# ADC.net
KiCad netlist of a schematic drawn in EasyEDA Pro
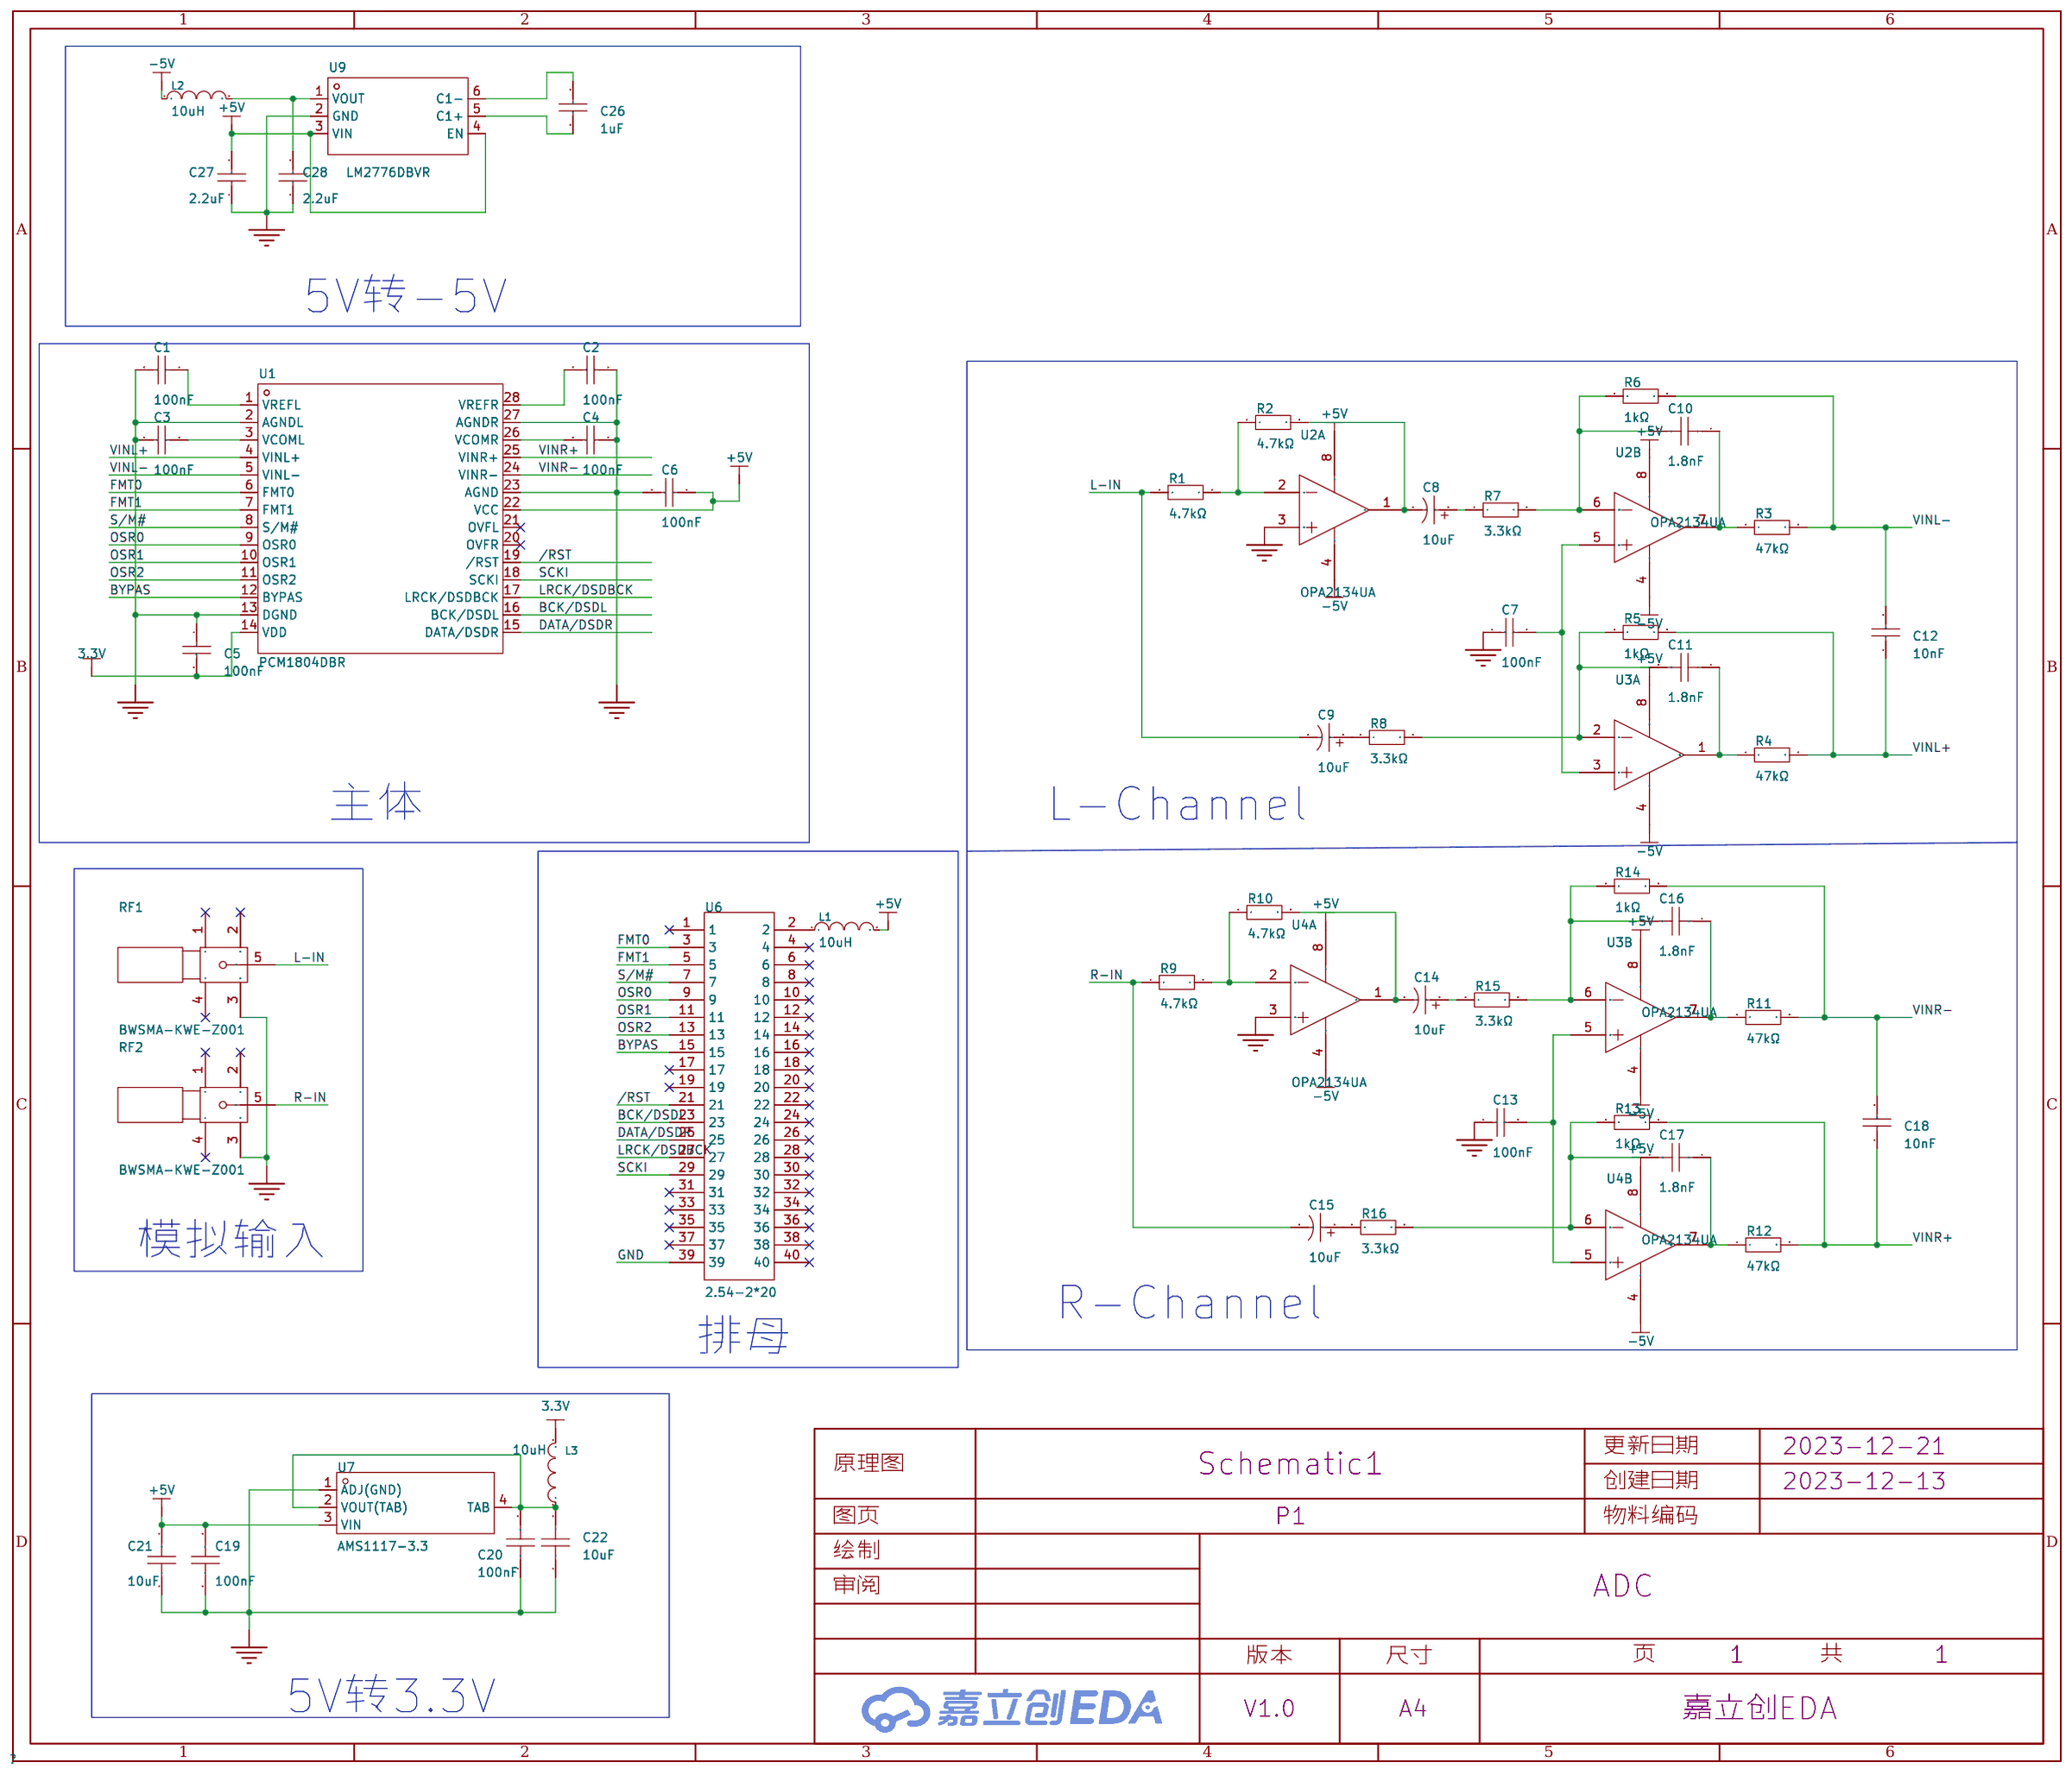
[diagram p0: schematic sheet]

(export (version "E")
  (design (tool "Eeschema 10.0.6"))
  (components
    (comp (ref "C1")
      (value "100nF")
      (footprint "easyedapro:C0805")
      (description "容值:100nF;精度:±10%;额定电压:50V;材质(温度系数):X7R;")
      (fields
        (field (name "Manufacturer Part") "CC0603KRX7R9BB104")
        (field (name "Manufacturer") "YAGEO(国巨)")
      )
      (libsource (lib "easyedapro") (part "CC0805KRX7R9BB104"))
    )
    (comp (ref "C2")
      (value "100nF")
      (footprint "easyedapro:C0805")
      (description "容值:100nF;精度:±10%;额定电压:50V;材质(温度系数):X7R;")
      (fields
        (field (name "Manufacturer Part") "CC0603KRX7R9BB104")
        (field (name "Manufacturer") "YAGEO(国巨)")
      )
      (libsource (lib "easyedapro") (part "CC0805KRX7R9BB104"))
    )
    (comp (ref "C3")
      (value "100nF")
      (footprint "easyedapro:C0805")
      (description "容值:100nF;精度:±10%;额定电压:50V;材质(温度系数):X7R;")
      (fields
        (field (name "Manufacturer Part") "CC0603KRX7R9BB104")
        (field (name "Manufacturer") "YAGEO(国巨)")
      )
      (libsource (lib "easyedapro") (part "CC0805KRX7R9BB104"))
    )
    (comp (ref "C4")
      (value "100nF")
      (footprint "easyedapro:C0805")
      (description "容值:100nF;精度:±10%;额定电压:50V;材质(温度系数):X7R;")
      (fields
        (field (name "Manufacturer Part") "CC0603KRX7R9BB104")
        (field (name "Manufacturer") "YAGEO(国巨)")
      )
      (libsource (lib "easyedapro") (part "CC0805KRX7R9BB104"))
    )
    (comp (ref "C5")
      (value "100nF")
      (footprint "easyedapro:C0805")
      (description "容值:100nF;精度:±10%;额定电压:50V;材质(温度系数):X7R;")
      (fields
        (field (name "Manufacturer Part") "CC0603KRX7R9BB104")
        (field (name "Manufacturer") "YAGEO(国巨)")
      )
      (libsource (lib "easyedapro") (part "CC0805KRX7R9BB104"))
    )
    (comp (ref "C6")
      (value "100nF")
      (footprint "easyedapro:C0805")
      (description "容值:100nF;精度:±10%;额定电压:50V;材质(温度系数):X7R;")
      (fields
        (field (name "Manufacturer Part") "CC0603KRX7R9BB104")
        (field (name "Manufacturer") "YAGEO(国巨)")
      )
      (libsource (lib "easyedapro") (part "CC0805KRX7R9BB104"))
    )
    (comp (ref "C7")
      (value "100nF")
      (footprint "easyedapro:C0805")
      (description "容值:100nF;精度:±10%;额定电压:50V;材质(温度系数):X7R;")
      (fields
        (field (name "Manufacturer Part") "CC0603KRX7R9BB104")
        (field (name "Manufacturer") "YAGEO(国巨)")
      )
      (libsource (lib "easyedapro") (part "CC0805KRX7R9BB104"))
    )
    (comp (ref "C8")
      (value "10uF")
      (footprint "easyedapro:CAP-SMD_BD6.3-L6.6-W6.6-FD")
      (description "容值:10uF;精度:±20%;额定电压:100V;纹波电流:38mA@120Hz;等效串联电阻:-;")
      (fields (field (name "Manufacturer Part") "RVT2A100M0607") (field (name "Manufacturer") "ROQANG(容强)"))
      (libsource (lib "easyedapro") (part "RVT2A100M0607"))
    )
    (comp (ref "C9")
      (value "10uF")
      (footprint "easyedapro:CAP-SMD_BD6.3-L6.6-W6.6-FD")
      (description "容值:10uF;精度:±20%;额定电压:100V;纹波电流:38mA@120Hz;等效串联电阻:-;")
      (fields (field (name "Manufacturer Part") "RVT2A100M0607") (field (name "Manufacturer") "ROQANG(容强)"))
      (libsource (lib "easyedapro") (part "RVT2A100M0607"))
    )
    (comp (ref "C10")
      (value "1.8nF")
      (footprint "easyedapro:C0201")
      (description "容值:1.8nF;精度:±10%;额定电压:25V;材质(温度系数):X7R;")
      (fields (field (name "Manufacturer Part") "0603B182K500NT") (field (name "Manufacturer") "FH(风华)"))
      (libsource (lib "easyedapro") (part "GRM033R71E182KA12D"))
    )
    (comp (ref "C11")
      (value "1.8nF")
      (footprint "easyedapro:C0201")
      (description "容值:1.8nF;精度:±10%;额定电压:25V;材质(温度系数):X7R;")
      (fields (field (name "Manufacturer Part") "0603B182K500NT") (field (name "Manufacturer") "FH(风华)"))
      (libsource (lib "easyedapro") (part "GRM033R71E182KA12D"))
    )
    (comp (ref "C12")
      (value "10nF")
      (footprint "easyedapro:C0402")
      (description "容值:10nF;精度:±10%;额定电压:50V;材质(温度系数):X7R;")
      (fields
        (field (name "Manufacturer Part") "CC0603KRX7R9BB103")
        (field (name "Manufacturer") "YAGEO(国巨)")
      )
      (libsource (lib "easyedapro") (part "CC0402KRX7R9BB103"))
    )
    (comp (ref "C13")
      (value "100nF")
      (footprint "easyedapro:C0805")
      (description "容值:100nF;精度:±10%;额定电压:50V;材质(温度系数):X7R;")
      (fields
        (field (name "Manufacturer Part") "CC0603KRX7R9BB104")
        (field (name "Manufacturer") "YAGEO(国巨)")
      )
      (libsource (lib "easyedapro") (part "CC0805KRX7R9BB104"))
    )
    (comp (ref "C14")
      (value "10uF")
      (footprint "easyedapro:CAP-SMD_BD6.3-L6.6-W6.6-FD")
      (description "容值:10uF;精度:±20%;额定电压:100V;纹波电流:38mA@120Hz;等效串联电阻:-;")
      (fields (field (name "Manufacturer Part") "RVT2A100M0607") (field (name "Manufacturer") "ROQANG(容强)"))
      (libsource (lib "easyedapro") (part "RVT2A100M0607"))
    )
    (comp (ref "C15")
      (value "10uF")
      (footprint "easyedapro:CAP-SMD_BD6.3-L6.6-W6.6-FD")
      (description "容值:10uF;精度:±20%;额定电压:100V;纹波电流:38mA@120Hz;等效串联电阻:-;")
      (fields (field (name "Manufacturer Part") "RVT2A100M0607") (field (name "Manufacturer") "ROQANG(容强)"))
      (libsource (lib "easyedapro") (part "RVT2A100M0607"))
    )
    (comp (ref "C16")
      (value "1.8nF")
      (footprint "easyedapro:C0201")
      (description "容值:1.8nF;精度:±10%;额定电压:25V;材质(温度系数):X7R;")
      (fields (field (name "Manufacturer Part") "0603B182K500NT") (field (name "Manufacturer") "FH(风华)"))
      (libsource (lib "easyedapro") (part "GRM033R71E182KA12D"))
    )
    (comp (ref "C17")
      (value "1.8nF")
      (footprint "easyedapro:C0201")
      (description "容值:1.8nF;精度:±10%;额定电压:25V;材质(温度系数):X7R;")
      (fields (field (name "Manufacturer Part") "0603B182K500NT") (field (name "Manufacturer") "FH(风华)"))
      (libsource (lib "easyedapro") (part "GRM033R71E182KA12D"))
    )
    (comp (ref "C18")
      (value "10nF")
      (footprint "easyedapro:C0402")
      (description "容值:10nF;精度:±10%;额定电压:50V;材质(温度系数):X7R;")
      (fields
        (field (name "Manufacturer Part") "CC0603KRX7R9BB103")
        (field (name "Manufacturer") "YAGEO(国巨)")
      )
      (libsource (lib "easyedapro") (part "CC0402KRX7R9BB103"))
    )
    (comp (ref "C19")
      (value "100nF")
      (footprint "easyedapro:C0603")
      (description "容值:100nF;精度:±10%;额定电压:50V;材质(温度系数):X7R;")
      (fields
        (field (name "Manufacturer Part") "CC0603KRX7R9BB104")
        (field (name "Manufacturer") "YAGEO(国巨)")
      )
      (libsource (lib "easyedapro") (part "CC0603KRX7R9BB104"))
    )
    (comp (ref "C20")
      (value "100nF")
      (footprint "easyedapro:C0603")
      (description "容值:100nF;精度:±10%;额定电压:50V;材质(温度系数):X7R;")
      (fields
        (field (name "Manufacturer Part") "CC0603KRX7R9BB104")
        (field (name "Manufacturer") "YAGEO(国巨)")
      )
      (libsource (lib "easyedapro") (part "CC0603KRX7R9BB104"))
    )
    (comp (ref "C21")
      (value "10uF")
      (footprint "easyedapro:C0603")
      (description "容值:10uF;精度:±10%;额定电压:10V;材质(温度系数):X5R;")
      (fields
        (field (name "Manufacturer Part") "CL10A106KP8NNNC")
        (field (name "Manufacturer") "SAMSUNG(三星)")
      )
      (libsource (lib "easyedapro") (part "CL10A106KP8NNNC"))
    )
    (comp (ref "C22")
      (value "10uF")
      (footprint "easyedapro:C0603")
      (description "容值:10uF;精度:±10%;额定电压:10V;材质(温度系数):X5R;")
      (fields
        (field (name "Manufacturer Part") "CL10A106KP8NNNC")
        (field (name "Manufacturer") "SAMSUNG(三星)")
      )
      (libsource (lib "easyedapro") (part "CL10A106KP8NNNC"))
    )
    (comp (ref "C26")
      (value "1uF")
      (footprint "easyedapro:C0603")
      (description "容值:1uF;精度:±10%;额定电压:50V;材质(温度系数):X5R;")
      (fields
        (field (name "Manufacturer Part") "CL10A105KB8NNNC")
        (field (name "Manufacturer") "SAMSUNG(三星)")
      )
      (libsource (lib "easyedapro") (part "CL10A105KB8NNNC"))
    )
    (comp (ref "C27")
      (value "2.2uF")
      (footprint "easyedapro:C0603")
      (description "容值:2.2uF;精度:±10%;额定电压:16V;材质(温度系数):X5R;")
      (fields
        (field (name "Manufacturer Part") "CL10A225KO8NNNC")
        (field (name "Manufacturer") "SAMSUNG(三星)")
      )
      (libsource (lib "easyedapro") (part "CL10A225KO8NNNC"))
    )
    (comp (ref "C28")
      (value "2.2uF")
      (footprint "easyedapro:C0603")
      (description "容值:2.2uF;精度:±10%;额定电压:16V;材质(温度系数):X5R;")
      (fields
        (field (name "Manufacturer Part") "CL10A225KO8NNNC")
        (field (name "Manufacturer") "SAMSUNG(三星)")
      )
      (libsource (lib "easyedapro") (part "CL10A225KO8NNNC"))
    )
    (comp (ref "L1")
      (value "10uH")
      (footprint "easyedapro:L0603")
      (description "电感值:10uH;精度:±10%;额定电流:3mA;饱和电流(Isat):-;直流电阻(DCR):1.85Ω;")
      (fields
        (field (name "Manufacturer Part") "SDFL1608S100KTF")
        (field (name "Manufacturer") "Sunlord(顺络)")
      )
      (libsource (lib "easyedapro") (part "SDFL1608S100KTF"))
    )
    (comp (ref "L2")
      (value "10uH")
      (footprint "easyedapro:L0603")
      (description "电感值:10uH;精度:±10%;额定电流:3mA;饱和电流(Isat):-;直流电阻(DCR):1.85Ω;")
      (fields
        (field (name "Manufacturer Part") "SDFL1608S100KTF")
        (field (name "Manufacturer") "Sunlord(顺络)")
      )
      (libsource (lib "easyedapro") (part "SDFL1608S100KTF"))
    )
    (comp (ref "L3")
      (value "10uH")
      (footprint "easyedapro:L0603")
      (description "电感值:10uH;精度:±10%;额定电流:3mA;饱和电流(Isat):-;直流电阻(DCR):1.85Ω;")
      (fields
        (field (name "Manufacturer Part") "SDFL1608S100KTF")
        (field (name "Manufacturer") "Sunlord(顺络)")
      )
      (libsource (lib "easyedapro") (part "SDFL1608S100KTF"))
    )
    (comp (ref "R1")
      (value "4.7kΩ")
      (footprint "easyedapro:R0603")
      (description "阻值:4.7kΩ;精度:±1%;功率:100mW;温度系数:±100ppm/°C;电阻类型:厚膜电阻;")
      (fields
        (field (name "Manufacturer Part") "0603WAF4701T5E")
        (field (name "Manufacturer") "UNI-ROYAL(厚声)")
      )
      (libsource (lib "easyedapro") (part "0603WAF4701T5E"))
    )
    (comp (ref "R2")
      (value "4.7kΩ")
      (footprint "easyedapro:R0603")
      (description "阻值:4.7kΩ;精度:±1%;功率:100mW;温度系数:±100ppm/°C;电阻类型:厚膜电阻;")
      (fields
        (field (name "Manufacturer Part") "0603WAF4701T5E")
        (field (name "Manufacturer") "UNI-ROYAL(厚声)")
      )
      (libsource (lib "easyedapro") (part "0603WAF4701T5E"))
    )
    (comp (ref "R3")
      (value "47kΩ")
      (footprint "easyedapro:R0603")
      (description "阻值:47kΩ;精度:±1%;功率:100mW;温度系数:±100ppm/°C;电阻类型:厚膜电阻;")
      (fields
        (field (name "Manufacturer Part") "0603WAF4702T5E")
        (field (name "Manufacturer") "UNI-ROYAL(厚声)")
      )
      (libsource (lib "easyedapro") (part "0603WAF4702T5E"))
    )
    (comp (ref "R4")
      (value "47kΩ")
      (footprint "easyedapro:R0603")
      (description "阻值:47kΩ;精度:±1%;功率:100mW;温度系数:±100ppm/°C;电阻类型:厚膜电阻;")
      (fields
        (field (name "Manufacturer Part") "0603WAF4702T5E")
        (field (name "Manufacturer") "UNI-ROYAL(厚声)")
      )
      (libsource (lib "easyedapro") (part "0603WAF4702T5E"))
    )
    (comp (ref "R5")
      (value "1kΩ")
      (footprint "easyedapro:R0805")
      (description "阻值:1kΩ;精度:±1%;功率:125mW;温度系数:±100ppm/°C;电阻类型:厚膜电阻;")
      (fields
        (field (name "Manufacturer Part") "0603WAF1001T5E")
        (field (name "Manufacturer") "UNI-ROYAL(厚声)")
      )
      (libsource (lib "easyedapro") (part "0805W8F1001T5E"))
    )
    (comp (ref "R6")
      (value "1kΩ")
      (footprint "easyedapro:R0805")
      (description "阻值:1kΩ;精度:±1%;功率:125mW;温度系数:±100ppm/°C;电阻类型:厚膜电阻;")
      (fields
        (field (name "Manufacturer Part") "0603WAF1001T5E")
        (field (name "Manufacturer") "UNI-ROYAL(厚声)")
      )
      (libsource (lib "easyedapro") (part "0805W8F1001T5E"))
    )
    (comp (ref "R7")
      (value "3.3kΩ")
      (footprint "easyedapro:R0603")
      (description "阻值:3.3kΩ;精度:±1%;功率:100mW;温度系数:±100ppm/°C;电阻类型:厚膜电阻;")
      (fields
        (field (name "Manufacturer Part") "0603WAF3301T5E")
        (field (name "Manufacturer") "UNI-ROYAL(厚声)")
      )
      (libsource (lib "easyedapro") (part "0603WAF3301T5E"))
    )
    (comp (ref "R8")
      (value "3.3kΩ")
      (footprint "easyedapro:R0603")
      (description "阻值:3.3kΩ;精度:±1%;功率:100mW;温度系数:±100ppm/°C;电阻类型:厚膜电阻;")
      (fields
        (field (name "Manufacturer Part") "0603WAF3301T5E")
        (field (name "Manufacturer") "UNI-ROYAL(厚声)")
      )
      (libsource (lib "easyedapro") (part "0603WAF3301T5E"))
    )
    (comp (ref "R9")
      (value "4.7kΩ")
      (footprint "easyedapro:R0603")
      (description "阻值:4.7kΩ;精度:±1%;功率:100mW;温度系数:±100ppm/°C;电阻类型:厚膜电阻;")
      (fields
        (field (name "Manufacturer Part") "0603WAF4701T5E")
        (field (name "Manufacturer") "UNI-ROYAL(厚声)")
      )
      (libsource (lib "easyedapro") (part "0603WAF4701T5E"))
    )
    (comp (ref "R10")
      (value "4.7kΩ")
      (footprint "easyedapro:R0603")
      (description "阻值:4.7kΩ;精度:±1%;功率:100mW;温度系数:±100ppm/°C;电阻类型:厚膜电阻;")
      (fields
        (field (name "Manufacturer Part") "0603WAF4701T5E")
        (field (name "Manufacturer") "UNI-ROYAL(厚声)")
      )
      (libsource (lib "easyedapro") (part "0603WAF4701T5E"))
    )
    (comp (ref "R11")
      (value "47kΩ")
      (footprint "easyedapro:R0603")
      (description "阻值:47kΩ;精度:±1%;功率:100mW;温度系数:±100ppm/°C;电阻类型:厚膜电阻;")
      (fields
        (field (name "Manufacturer Part") "0603WAF4702T5E")
        (field (name "Manufacturer") "UNI-ROYAL(厚声)")
      )
      (libsource (lib "easyedapro") (part "0603WAF4702T5E"))
    )
    (comp (ref "R12")
      (value "47kΩ")
      (footprint "easyedapro:R0603")
      (description "阻值:47kΩ;精度:±1%;功率:100mW;温度系数:±100ppm/°C;电阻类型:厚膜电阻;")
      (fields
        (field (name "Manufacturer Part") "0603WAF4702T5E")
        (field (name "Manufacturer") "UNI-ROYAL(厚声)")
      )
      (libsource (lib "easyedapro") (part "0603WAF4702T5E"))
    )
    (comp (ref "R13")
      (value "1kΩ")
      (footprint "easyedapro:R0805")
      (description "阻值:1kΩ;精度:±1%;功率:125mW;温度系数:±100ppm/°C;电阻类型:厚膜电阻;")
      (fields
        (field (name "Manufacturer Part") "0603WAF1001T5E")
        (field (name "Manufacturer") "UNI-ROYAL(厚声)")
      )
      (libsource (lib "easyedapro") (part "0805W8F1001T5E"))
    )
    (comp (ref "R14")
      (value "1kΩ")
      (footprint "easyedapro:R0805")
      (description "阻值:1kΩ;精度:±1%;功率:125mW;温度系数:±100ppm/°C;电阻类型:厚膜电阻;")
      (fields
        (field (name "Manufacturer Part") "0603WAF1001T5E")
        (field (name "Manufacturer") "UNI-ROYAL(厚声)")
      )
      (libsource (lib "easyedapro") (part "0805W8F1001T5E"))
    )
    (comp (ref "R15")
      (value "3.3kΩ")
      (footprint "easyedapro:R0603")
      (description "阻值:3.3kΩ;精度:±1%;功率:100mW;温度系数:±100ppm/°C;电阻类型:厚膜电阻;")
      (fields
        (field (name "Manufacturer Part") "0603WAF3301T5E")
        (field (name "Manufacturer") "UNI-ROYAL(厚声)")
      )
      (libsource (lib "easyedapro") (part "0603WAF3301T5E"))
    )
    (comp (ref "R16")
      (value "3.3kΩ")
      (footprint "easyedapro:R0603")
      (description "阻值:3.3kΩ;精度:±1%;功率:100mW;温度系数:±100ppm/°C;电阻类型:厚膜电阻;")
      (fields
        (field (name "Manufacturer Part") "0603WAF3301T5E")
        (field (name "Manufacturer") "UNI-ROYAL(厚声)")
      )
      (libsource (lib "easyedapro") (part "0603WAF3301T5E"))
    )
    (comp (ref "RF1")
      (value "BWSMA-KWE-Z001")
      (footprint "easyedapro:SMA-TH_BWSMA-KWE-Z001")
      (fields (field (name "Manufacturer") "BAT WIRELESS(蝙蝠无线)"))
      (libsource (lib "easyedapro") (part "BWSMA-KWE-Z001"))
    )
    (comp (ref "RF2")
      (value "BWSMA-KWE-Z001")
      (footprint "easyedapro:SMA-TH_BWSMA-KWE-Z001")
      (fields (field (name "Manufacturer") "BAT WIRELESS(蝙蝠无线)"))
      (libsource (lib "easyedapro") (part "BWSMA-KWE-Z001"))
    )
    (comp (ref "U1")
      (value "PCM1804DBR")
      (footprint "easyedapro:SSOP-28_L10.2-W5.3-P0.65-LS7.8-BL")
      (description "供电电压:3V~3.6V；4.75V~5.25V;分辨率(位):24;接口类型:I2S;")
      (fields (field (name "Manufacturer") "TI(德州仪器)"))
      (libsource (lib "easyedapro") (part "PCM1804DBR"))
    )
    (comp (ref "U2")
      (value "OPA2134UA")
      (footprint "easyedapro:DIP-8_L9.6-W6.4-P2.54-LS7.6-BL-1")
      (description "功放类型:-;输出功率:-;")
      (fields (field (name "Manufacturer") "TI(德州仪器)"))
      (libsource (lib "easyedapro") (part "OPA2134PA"))
    )
    (comp (ref "U3")
      (value "OPA2134UA")
      (footprint "easyedapro:DIP-8_L9.6-W6.4-P2.54-LS7.6-BL-1")
      (description "功放类型:-;输出功率:-;")
      (fields (field (name "Manufacturer") "TI(德州仪器)"))
      (libsource (lib "easyedapro") (part "OPA2134PA"))
    )
    (comp (ref "U4")
      (value "OPA2134UA")
      (footprint "easyedapro:DIP-8_L9.6-W6.4-P2.54-LS7.6-BL-1")
      (description "功放类型:-;输出功率:-;")
      (fields (field (name "Manufacturer") "TI(德州仪器)"))
      (libsource (lib "easyedapro") (part "OPA2134PA"))
    )
    (comp (ref "U6")
      (value "2.54-2*20")
      (footprint "easyedapro:HDR-TH_40P-P2.54-V-F-R2-C20-S2.54")
      (fields (field (name "Manufacturer") "ZHOURI(洲日)"))
      (libsource (lib "easyedapro") (part "2.54-2*20"))
    )
    (comp (ref "U7")
      (value "AMS1117-3.3")
      (footprint "easyedapro:SOT-223-4_L6.5-W3.5-P2.30-LS7.0-BR")
      (description "输出类型:固定;最大输入电压:18V;输出电压:3.3V;输出电流:1A;电源纹波抑制比(PSRR):60dB@(120Hz);输出极性:正;")
      (fields (field (name "Manufacturer") "UMW(友台半导体)"))
      (libsource (lib "easyedapro") (part "AMS1117-3.3_C347222"))
    )
    (comp (ref "U9")
      (value "LM2776DBVR")
      (footprint "easyedapro:SOT-23-6_L2.9-W1.6-P0.95-LS2.8-BR")
      (description "功能类型:电荷泵;输出类型:固定;输入电压:2.7V~5.5V;输出电压:-5.5V~-2.7V;输出电流(最大值):200mA;")
      (fields (field (name "Manufacturer") "TI(德州仪器)"))
      (libsource (lib "easyedapro") (part "LM2776DBVR"))
    )
  )
  (nets
    (net (code "1") (name "+5V") (class "Default")
      (node (ref "C19") (pin "2") (pinfunction "2_2") (pintype "unspecified"))
      (node (ref "C21") (pin "2") (pinfunction "2_2") (pintype "unspecified"))
      (node (ref "C27") (pin "2") (pinfunction "2_2") (pintype "input"))
      (node (ref "C6") (pin "1") (pinfunction "1_1") (pintype "input"))
      (node (ref "L1") (pin "2") (pinfunction "2_2") (pintype "input"))
      (node (ref "U1") (pin "22") (pinfunction "VCC_22") (pintype "unspecified"))
      (node (ref "U2") (pin "8") (pinfunction "V+_8") (pintype "input"))
      (node (ref "U3") (pin "8") (pinfunction "V+_8") (pintype "input"))
      (node (ref "U4") (pin "8") (pinfunction "V+_8") (pintype "input"))
      (node (ref "U7") (pin "3") (pinfunction "VIN_3") (pintype "unspecified"))
      (node (ref "U9") (pin "3") (pinfunction "VIN_3") (pintype "unspecified"))
      (node (ref "U9") (pin "4") (pinfunction "EN_4") (pintype "unspecified"))
    )
    (net (code "2") (name "-5V") (class "Default")
      (node (ref "L2") (pin "1") (pinfunction "1_1") (pintype "input"))
      (node (ref "U2") (pin "4") (pinfunction "V-_4") (pintype "input"))
      (node (ref "U3") (pin "4") (pinfunction "V-_4") (pintype "input"))
      (node (ref "U4") (pin "4") (pinfunction "V-_4") (pintype "input"))
    )
    (net (code "3") (name "/BCK{slash}DSDL") (class "Default")
      (node (ref "U1") (pin "16") (pinfunction "BCK/DSDL_16") (pintype "unspecified"))
      (node (ref "U6") (pin "23") (pinfunction "23_23") (pintype "unspecified"))
    )
    (net (code "4") (name "/BYPAS") (class "Default")
      (node (ref "U1") (pin "12") (pinfunction "BYPAS_12") (pintype "unspecified"))
      (node (ref "U6") (pin "15") (pinfunction "15_15") (pintype "unspecified"))
    )
    (net (code "5") (name "/DATA{slash}DSDR") (class "Default")
      (node (ref "U1") (pin "15") (pinfunction "DATA/DSDR_15") (pintype "unspecified"))
      (node (ref "U6") (pin "25") (pinfunction "25_25") (pintype "unspecified"))
    )
    (net (code "6") (name "/FMT0") (class "Default")
      (node (ref "U1") (pin "6") (pinfunction "FMT0_6") (pintype "unspecified"))
      (node (ref "U6") (pin "3") (pinfunction "3_3") (pintype "unspecified"))
    )
    (net (code "7") (name "/FMT1") (class "Default")
      (node (ref "U1") (pin "7") (pinfunction "FMT1_7") (pintype "unspecified"))
      (node (ref "U6") (pin "5") (pinfunction "5_5") (pintype "unspecified"))
    )
    (net (code "8") (name "/L-IN") (class "Default")
      (node (ref "C9") (pin "2") (pinfunction "2_2") (pintype "input"))
      (node (ref "R1") (pin "1") (pinfunction "1_1") (pintype "input"))
      (node (ref "RF1") (pin "5") (pinfunction "5_5") (pintype "unspecified"))
    )
    (net (code "9") (name "/LRCK{slash}DSDBCK") (class "Default")
      (node (ref "U1") (pin "17") (pinfunction "LRCK/DSDBCK_17") (pintype "unspecified"))
      (node (ref "U6") (pin "27") (pinfunction "27_27") (pintype "unspecified"))
    )
    (net (code "10") (name "/OSR0") (class "Default")
      (node (ref "U1") (pin "9") (pinfunction "OSR0_9") (pintype "unspecified"))
      (node (ref "U6") (pin "9") (pinfunction "9_9") (pintype "unspecified"))
    )
    (net (code "11") (name "/OSR1") (class "Default")
      (node (ref "U1") (pin "10") (pinfunction "OSR1_10") (pintype "unspecified"))
      (node (ref "U6") (pin "11") (pinfunction "11_11") (pintype "unspecified"))
    )
    (net (code "12") (name "/OSR2") (class "Default")
      (node (ref "U1") (pin "11") (pinfunction "OSR2_11") (pintype "unspecified"))
      (node (ref "U6") (pin "13") (pinfunction "13_13") (pintype "unspecified"))
    )
    (net (code "13") (name "/R-IN") (class "Default")
      (node (ref "C15") (pin "2") (pinfunction "2_2") (pintype "input"))
      (node (ref "R9") (pin "1") (pinfunction "1_1") (pintype "input"))
      (node (ref "RF2") (pin "5") (pinfunction "5_5") (pintype "unspecified"))
    )
    (net (code "14") (name "/SCKI") (class "Default")
      (node (ref "U1") (pin "18") (pinfunction "SCKI_18") (pintype "unspecified"))
      (node (ref "U6") (pin "29") (pinfunction "29_29") (pintype "unspecified"))
    )
    (net (code "15") (name "/S{slash}M#") (class "Default")
      (node (ref "U1") (pin "8") (pinfunction "S/M#_8") (pintype "unspecified"))
      (node (ref "U6") (pin "7") (pinfunction "7_7") (pintype "unspecified"))
    )
    (net (code "16") (name "/VINL+") (class "Default")
      (node (ref "C12") (pin "1") (pinfunction "1_1") (pintype "input"))
      (node (ref "R4") (pin "2") (pinfunction "2_2") (pintype "input"))
      (node (ref "R5") (pin "2") (pinfunction "2_2") (pintype "input"))
      (node (ref "U1") (pin "4") (pinfunction "VINL+_4") (pintype "unspecified"))
    )
    (net (code "17") (name "/VINL-") (class "Default")
      (node (ref "C12") (pin "2") (pinfunction "2_2") (pintype "input"))
      (node (ref "R3") (pin "2") (pinfunction "2_2") (pintype "input"))
      (node (ref "R6") (pin "2") (pinfunction "2_2") (pintype "input"))
      (node (ref "U1") (pin "5") (pinfunction "VINL-_5") (pintype "unspecified"))
    )
    (net (code "18") (name "/VINR+") (class "Default")
      (node (ref "C18") (pin "1") (pinfunction "1_1") (pintype "input"))
      (node (ref "R12") (pin "2") (pinfunction "2_2") (pintype "input"))
      (node (ref "R13") (pin "2") (pinfunction "2_2") (pintype "input"))
      (node (ref "U1") (pin "25") (pinfunction "VINR+_25") (pintype "unspecified"))
    )
    (net (code "19") (name "/VINR-") (class "Default")
      (node (ref "C18") (pin "2") (pinfunction "2_2") (pintype "input"))
      (node (ref "R11") (pin "2") (pinfunction "2_2") (pintype "input"))
      (node (ref "R14") (pin "2") (pinfunction "2_2") (pintype "input"))
      (node (ref "U1") (pin "24") (pinfunction "VINR-_24") (pintype "unspecified"))
    )
    (net (code "20") (name "/{slash}RST") (class "Default")
      (node (ref "U1") (pin "19") (pinfunction "/RST_19") (pintype "unspecified"))
      (node (ref "U6") (pin "21") (pinfunction "21_21") (pintype "unspecified"))
    )
    (net (code "21") (name "3.3V") (class "Default")
      (node (ref "C5") (pin "2") (pinfunction "2_2") (pintype "input"))
      (node (ref "L3") (pin "2") (pinfunction "2_2") (pintype "input"))
      (node (ref "U1") (pin "14") (pinfunction "VDD_14") (pintype "unspecified"))
    )
    (net (code "22") (name "GND") (class "Default")
      (node (ref "C1") (pin "2") (pinfunction "2_2") (pintype "input"))
      (node (ref "C13") (pin "1") (pinfunction "1_1") (pintype "input"))
      (node (ref "C19") (pin "1") (pinfunction "1_1") (pintype "unspecified"))
      (node (ref "C2") (pin "1") (pinfunction "1_1") (pintype "input"))
      (node (ref "C20") (pin "1") (pinfunction "1_1") (pintype "unspecified"))
      (node (ref "C21") (pin "1") (pinfunction "1_1") (pintype "unspecified"))
      (node (ref "C22") (pin "1") (pinfunction "1_1") (pintype "unspecified"))
      (node (ref "C27") (pin "1") (pinfunction "1_1") (pintype "input"))
      (node (ref "C28") (pin "1") (pinfunction "1_1") (pintype "input"))
      (node (ref "C3") (pin "2") (pinfunction "2_2") (pintype "input"))
      (node (ref "C4") (pin "1") (pinfunction "1_1") (pintype "input"))
      (node (ref "C5") (pin "1") (pinfunction "1_1") (pintype "input"))
      (node (ref "C6") (pin "2") (pinfunction "2_2") (pintype "input"))
      (node (ref "C7") (pin "1") (pinfunction "1_1") (pintype "input"))
      (node (ref "RF1") (pin "3") (pinfunction "3_3") (pintype "unspecified"))
      (node (ref "RF2") (pin "3") (pinfunction "3_3") (pintype "unspecified"))
      (node (ref "U1") (pin "13") (pinfunction "DGND_13") (pintype "unspecified"))
      (node (ref "U1") (pin "2") (pinfunction "AGNDL_2") (pintype "unspecified"))
      (node (ref "U1") (pin "23") (pinfunction "AGND_23") (pintype "unspecified"))
      (node (ref "U1") (pin "27") (pinfunction "AGNDR_27") (pintype "unspecified"))
      (node (ref "U2") (pin "3") (pinfunction "+IN_A_3") (pintype "input"))
      (node (ref "U4") (pin "3") (pinfunction "+IN_A_3") (pintype "input"))
      (node (ref "U6") (pin "39") (pinfunction "39_39") (pintype "unspecified"))
      (node (ref "U7") (pin "1") (pinfunction "ADJ(GND)_1") (pintype "unspecified"))
      (node (ref "U9") (pin "2") (pinfunction "GND_2") (pintype "unspecified"))
    )
    (net (code "23") (name "Net-(C8-Pad1)") (class "Default")
      (node (ref "C8") (pin "1") (pinfunction "1_1") (pintype "input"))
      (node (ref "R7") (pin "1") (pinfunction "1_1") (pintype "input"))
    )
    (net (code "24") (name "Net-(C9-Pad1)") (class "Default")
      (node (ref "C9") (pin "1") (pinfunction "1_1") (pintype "input"))
      (node (ref "R8") (pin "1") (pinfunction "1_1") (pintype "input"))
    )
    (net (code "25") (name "Net-(C14-Pad1)") (class "Default")
      (node (ref "C14") (pin "1") (pinfunction "1_1") (pintype "input"))
      (node (ref "R15") (pin "1") (pinfunction "1_1") (pintype "input"))
    )
    (net (code "26") (name "Net-(C15-Pad1)") (class "Default")
      (node (ref "C15") (pin "1") (pinfunction "1_1") (pintype "input"))
      (node (ref "R16") (pin "1") (pinfunction "1_1") (pintype "input"))
    )
    (net (code "27") (name "Net-(L1-Pad1)") (class "Default")
      (node (ref "L1") (pin "1") (pinfunction "1_1") (pintype "input"))
      (node (ref "U6") (pin "2") (pinfunction "2_2") (pintype "unspecified"))
    )
    (net (code "28") (name "Net-(U1-VCOML)") (class "Default")
      (node (ref "C3") (pin "1") (pinfunction "1_1") (pintype "input"))
      (node (ref "U1") (pin "3") (pinfunction "VCOML_3") (pintype "unspecified"))
    )
    (net (code "29") (name "Net-(U1-VCOMR)") (class "Default")
      (node (ref "C4") (pin "2") (pinfunction "2_2") (pintype "input"))
      (node (ref "U1") (pin "26") (pinfunction "VCOMR_26") (pintype "unspecified"))
    )
    (net (code "30") (name "Net-(U1-VREFL)") (class "Default")
      (node (ref "C1") (pin "1") (pinfunction "1_1") (pintype "input"))
      (node (ref "U1") (pin "1") (pinfunction "VREFL_1") (pintype "unspecified"))
    )
    (net (code "31") (name "Net-(U1-VREFR)") (class "Default")
      (node (ref "C2") (pin "2") (pinfunction "2_2") (pintype "input"))
      (node (ref "U1") (pin "28") (pinfunction "VREFR_28") (pintype "unspecified"))
    )
    (net (code "32") (name "Net-(U2A--IN_A)") (class "Default")
      (node (ref "R1") (pin "2") (pinfunction "2_2") (pintype "input"))
      (node (ref "R2") (pin "1") (pinfunction "1_1") (pintype "input"))
      (node (ref "U2") (pin "2") (pinfunction "-IN_A_2") (pintype "input"))
    )
    (net (code "33") (name "Net-(U2A-OUT_A)") (class "Default")
      (node (ref "C8") (pin "2") (pinfunction "2_2") (pintype "input"))
      (node (ref "R2") (pin "2") (pinfunction "2_2") (pintype "input"))
      (node (ref "U2") (pin "1") (pinfunction "OUT_A_1") (pintype "output"))
    )
    (net (code "34") (name "Net-(U2B-+IN_B)") (class "Default")
      (node (ref "C7") (pin "2") (pinfunction "2_2") (pintype "input"))
      (node (ref "U2") (pin "5") (pinfunction "+IN_B_5") (pintype "input"))
      (node (ref "U3") (pin "3") (pinfunction "+IN_A_3") (pintype "input"))
    )
    (net (code "35") (name "Net-(U2B--IN_B)") (class "Default")
      (node (ref "C10") (pin "2") (pinfunction "2_2") (pintype "unspecified"))
      (node (ref "R6") (pin "1") (pinfunction "1_1") (pintype "input"))
      (node (ref "R7") (pin "2") (pinfunction "2_2") (pintype "input"))
      (node (ref "U2") (pin "6") (pinfunction "-IN_B_6") (pintype "input"))
    )
    (net (code "36") (name "Net-(U2B-OUT_B)") (class "Default")
      (node (ref "C10") (pin "1") (pinfunction "1_1") (pintype "unspecified"))
      (node (ref "R3") (pin "1") (pinfunction "1_1") (pintype "input"))
      (node (ref "U2") (pin "7") (pinfunction "OUT_B_7") (pintype "output"))
    )
    (net (code "37") (name "Net-(U3A--IN_A)") (class "Default")
      (node (ref "C11") (pin "2") (pinfunction "2_2") (pintype "unspecified"))
      (node (ref "R5") (pin "1") (pinfunction "1_1") (pintype "input"))
      (node (ref "R8") (pin "2") (pinfunction "2_2") (pintype "input"))
      (node (ref "U3") (pin "2") (pinfunction "-IN_A_2") (pintype "input"))
    )
    (net (code "38") (name "Net-(U3A-OUT_A)") (class "Default")
      (node (ref "C11") (pin "1") (pinfunction "1_1") (pintype "unspecified"))
      (node (ref "R4") (pin "1") (pinfunction "1_1") (pintype "input"))
      (node (ref "U3") (pin "1") (pinfunction "OUT_A_1") (pintype "output"))
    )
    (net (code "39") (name "Net-(U3B-+IN_B)") (class "Default")
      (node (ref "C13") (pin "2") (pinfunction "2_2") (pintype "input"))
      (node (ref "U3") (pin "5") (pinfunction "+IN_B_5") (pintype "input"))
      (node (ref "U4") (pin "5") (pinfunction "+IN_B_5") (pintype "input"))
    )
    (net (code "40") (name "Net-(U3B--IN_B)") (class "Default")
      (node (ref "C16") (pin "2") (pinfunction "2_2") (pintype "unspecified"))
      (node (ref "R14") (pin "1") (pinfunction "1_1") (pintype "input"))
      (node (ref "R15") (pin "2") (pinfunction "2_2") (pintype "input"))
      (node (ref "U3") (pin "6") (pinfunction "-IN_B_6") (pintype "input"))
    )
    (net (code "41") (name "Net-(U3B-OUT_B)") (class "Default")
      (node (ref "C16") (pin "1") (pinfunction "1_1") (pintype "unspecified"))
      (node (ref "R11") (pin "1") (pinfunction "1_1") (pintype "input"))
      (node (ref "U3") (pin "7") (pinfunction "OUT_B_7") (pintype "output"))
    )
    (net (code "42") (name "Net-(U4A--IN_A)") (class "Default")
      (node (ref "R10") (pin "1") (pinfunction "1_1") (pintype "input"))
      (node (ref "R9") (pin "2") (pinfunction "2_2") (pintype "input"))
      (node (ref "U4") (pin "2") (pinfunction "-IN_A_2") (pintype "input"))
    )
    (net (code "43") (name "Net-(U4A-OUT_A)") (class "Default")
      (node (ref "C14") (pin "2") (pinfunction "2_2") (pintype "input"))
      (node (ref "R10") (pin "2") (pinfunction "2_2") (pintype "input"))
      (node (ref "U4") (pin "1") (pinfunction "OUT_A_1") (pintype "output"))
    )
    (net (code "44") (name "Net-(U4B--IN_B)") (class "Default")
      (node (ref "C17") (pin "2") (pinfunction "2_2") (pintype "unspecified"))
      (node (ref "R13") (pin "1") (pinfunction "1_1") (pintype "input"))
      (node (ref "R16") (pin "2") (pinfunction "2_2") (pintype "input"))
      (node (ref "U4") (pin "6") (pinfunction "-IN_B_6") (pintype "input"))
    )
    (net (code "45") (name "Net-(U4B-OUT_B)") (class "Default")
      (node (ref "C17") (pin "1") (pinfunction "1_1") (pintype "unspecified"))
      (node (ref "R12") (pin "1") (pinfunction "1_1") (pintype "input"))
      (node (ref "U4") (pin "7") (pinfunction "OUT_B_7") (pintype "output"))
    )
    (net (code "46") (name "Net-(U7-TAB)") (class "Default")
      (node (ref "C20") (pin "2") (pinfunction "2_2") (pintype "unspecified"))
      (node (ref "C22") (pin "2") (pinfunction "2_2") (pintype "unspecified"))
      (node (ref "L3") (pin "1") (pinfunction "1_1") (pintype "input"))
      (node (ref "U7") (pin "2") (pinfunction "VOUT(TAB)_2") (pintype "unspecified"))
      (node (ref "U7") (pin "4") (pinfunction "TAB_4") (pintype "unspecified"))
    )
    (net (code "47") (name "Net-(U9-C1+)") (class "Default")
      (node (ref "C26") (pin "1") (pinfunction "1_1") (pintype "input"))
      (node (ref "U9") (pin "5") (pinfunction "C1+_5") (pintype "unspecified"))
    )
    (net (code "48") (name "Net-(U9-C1-)") (class "Default")
      (node (ref "C26") (pin "2") (pinfunction "2_2") (pintype "input"))
      (node (ref "U9") (pin "6") (pinfunction "C1-_6") (pintype "unspecified"))
    )
    (net (code "49") (name "Net-(U9-VOUT)") (class "Default")
      (node (ref "C28") (pin "2") (pinfunction "2_2") (pintype "input"))
      (node (ref "L2") (pin "2") (pinfunction "2_2") (pintype "input"))
      (node (ref "U9") (pin "1") (pinfunction "VOUT_1") (pintype "unspecified"))
    )
    (net (code "50") (name "unconnected-(RF1-Pad1)") (class "Default")
      (node (ref "RF1") (pin "1") (pinfunction "1_1") (pintype "unspecified+no_connect"))
    )
    (net (code "51") (name "unconnected-(RF1-Pad2)") (class "Default")
      (node (ref "RF1") (pin "2") (pinfunction "2_2") (pintype "unspecified+no_connect"))
    )
    (net (code "52") (name "unconnected-(RF1-Pad4)") (class "Default")
      (node (ref "RF1") (pin "4") (pinfunction "4_4") (pintype "unspecified+no_connect"))
    )
    (net (code "53") (name "unconnected-(RF2-Pad1)") (class "Default")
      (node (ref "RF2") (pin "1") (pinfunction "1_1") (pintype "unspecified+no_connect"))
    )
    (net (code "54") (name "unconnected-(RF2-Pad2)") (class "Default")
      (node (ref "RF2") (pin "2") (pinfunction "2_2") (pintype "unspecified+no_connect"))
    )
    (net (code "55") (name "unconnected-(RF2-Pad4)") (class "Default")
      (node (ref "RF2") (pin "4") (pinfunction "4_4") (pintype "unspecified+no_connect"))
    )
    (net (code "56") (name "unconnected-(U1-OVFL-Pad21)") (class "Default")
      (node (ref "U1") (pin "21") (pinfunction "OVFL_21") (pintype "unspecified+no_connect"))
    )
    (net (code "57") (name "unconnected-(U1-OVFR-Pad20)") (class "Default")
      (node (ref "U1") (pin "20") (pinfunction "OVFR_20") (pintype "unspecified+no_connect"))
    )
    (net (code "58") (name "unconnected-(U6-Pad1)") (class "Default")
      (node (ref "U6") (pin "1") (pinfunction "1_1") (pintype "unspecified+no_connect"))
    )
    (net (code "59") (name "unconnected-(U6-Pad4)") (class "Default")
      (node (ref "U6") (pin "4") (pinfunction "4_4") (pintype "unspecified+no_connect"))
    )
    (net (code "60") (name "unconnected-(U6-Pad6)") (class "Default")
      (node (ref "U6") (pin "6") (pinfunction "6_6") (pintype "unspecified+no_connect"))
    )
    (net (code "61") (name "unconnected-(U6-Pad8)") (class "Default")
      (node (ref "U6") (pin "8") (pinfunction "8_8") (pintype "unspecified+no_connect"))
    )
    (net (code "62") (name "unconnected-(U6-Pad10)") (class "Default")
      (node (ref "U6") (pin "10") (pinfunction "10_10") (pintype "unspecified+no_connect"))
    )
    (net (code "63") (name "unconnected-(U6-Pad12)") (class "Default")
      (node (ref "U6") (pin "12") (pinfunction "12_12") (pintype "unspecified+no_connect"))
    )
    (net (code "64") (name "unconnected-(U6-Pad14)") (class "Default")
      (node (ref "U6") (pin "14") (pinfunction "14_14") (pintype "unspecified+no_connect"))
    )
    (net (code "65") (name "unconnected-(U6-Pad16)") (class "Default")
      (node (ref "U6") (pin "16") (pinfunction "16_16") (pintype "unspecified+no_connect"))
    )
    (net (code "66") (name "unconnected-(U6-Pad17)") (class "Default")
      (node (ref "U6") (pin "17") (pinfunction "17_17") (pintype "unspecified+no_connect"))
    )
    (net (code "67") (name "unconnected-(U6-Pad18)") (class "Default")
      (node (ref "U6") (pin "18") (pinfunction "18_18") (pintype "unspecified+no_connect"))
    )
    (net (code "68") (name "unconnected-(U6-Pad19)") (class "Default")
      (node (ref "U6") (pin "19") (pinfunction "19_19") (pintype "unspecified+no_connect"))
    )
    (net (code "69") (name "unconnected-(U6-Pad20)") (class "Default")
      (node (ref "U6") (pin "20") (pinfunction "20_20") (pintype "unspecified+no_connect"))
    )
    (net (code "70") (name "unconnected-(U6-Pad22)") (class "Default")
      (node (ref "U6") (pin "22") (pinfunction "22_22") (pintype "unspecified+no_connect"))
    )
    (net (code "71") (name "unconnected-(U6-Pad24)") (class "Default")
      (node (ref "U6") (pin "24") (pinfunction "24_24") (pintype "unspecified+no_connect"))
    )
    (net (code "72") (name "unconnected-(U6-Pad26)") (class "Default")
      (node (ref "U6") (pin "26") (pinfunction "26_26") (pintype "unspecified+no_connect"))
    )
    (net (code "73") (name "unconnected-(U6-Pad28)") (class "Default")
      (node (ref "U6") (pin "28") (pinfunction "28_28") (pintype "unspecified+no_connect"))
    )
    (net (code "74") (name "unconnected-(U6-Pad30)") (class "Default")
      (node (ref "U6") (pin "30") (pinfunction "30_30") (pintype "unspecified+no_connect"))
    )
    (net (code "75") (name "unconnected-(U6-Pad31)") (class "Default")
      (node (ref "U6") (pin "31") (pinfunction "31_31") (pintype "unspecified+no_connect"))
    )
    (net (code "76") (name "unconnected-(U6-Pad32)") (class "Default")
      (node (ref "U6") (pin "32") (pinfunction "32_32") (pintype "unspecified+no_connect"))
    )
    (net (code "77") (name "unconnected-(U6-Pad33)") (class "Default")
      (node (ref "U6") (pin "33") (pinfunction "33_33") (pintype "unspecified+no_connect"))
    )
    (net (code "78") (name "unconnected-(U6-Pad34)") (class "Default")
      (node (ref "U6") (pin "34") (pinfunction "34_34") (pintype "unspecified+no_connect"))
    )
    (net (code "79") (name "unconnected-(U6-Pad35)") (class "Default")
      (node (ref "U6") (pin "35") (pinfunction "35_35") (pintype "unspecified+no_connect"))
    )
    (net (code "80") (name "unconnected-(U6-Pad36)") (class "Default")
      (node (ref "U6") (pin "36") (pinfunction "36_36") (pintype "unspecified+no_connect"))
    )
    (net (code "81") (name "unconnected-(U6-Pad37)") (class "Default")
      (node (ref "U6") (pin "37") (pinfunction "37_37") (pintype "unspecified+no_connect"))
    )
    (net (code "82") (name "unconnected-(U6-Pad38)") (class "Default")
      (node (ref "U6") (pin "38") (pinfunction "38_38") (pintype "unspecified+no_connect"))
    )
    (net (code "83") (name "unconnected-(U6-Pad40)") (class "Default")
      (node (ref "U6") (pin "40") (pinfunction "40_40") (pintype "unspecified+no_connect"))
    )
  )
)
